# ESP32.net
KiCad netlist of a schematic drawn in Altium Designer
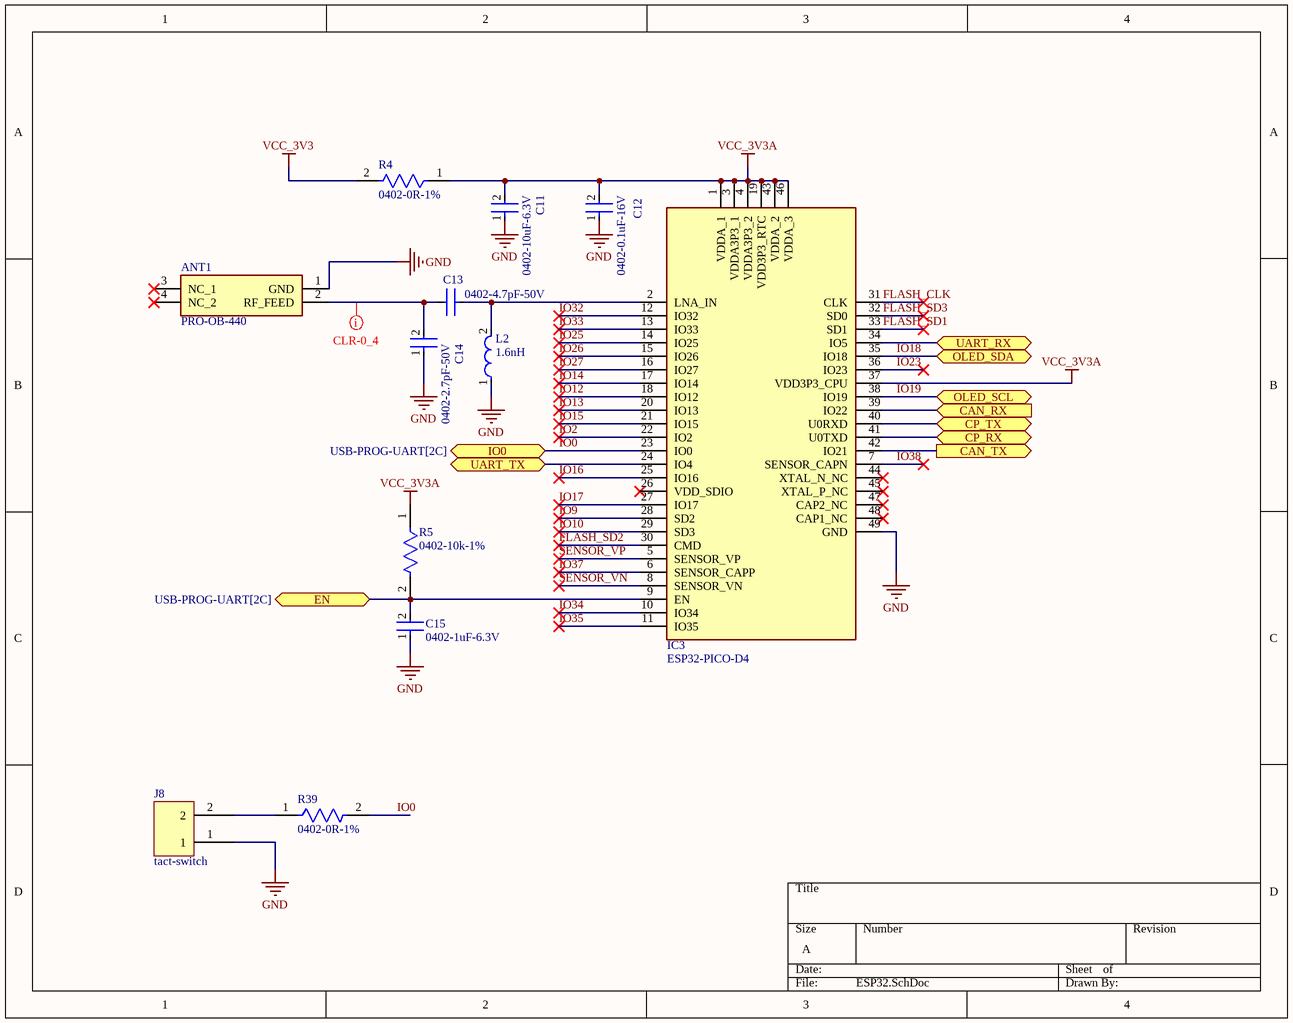
[diagram p0: ESP32.SchDoc]

(export (version "E")
  (design (tool "Eeschema 10.0.6"))
  (components
    (comp (ref "ANT1")
      (value "PRO-OB-440")
      (footprint "SamacSys:PRO-OB-440_1")
      (description "Antenna")
      (libsource (lib "SamacSys") (part "PRO-OB-440"))
    )
    (comp (ref "C11")
      (value "0402-10uF-6.3V")
      (footprint "FP-GRM155-0_05-IPC_A")
      (description "CAP CER 0.22UF 10V X5R 0402")
      (fields (field (name "VOLTAGE") "10V") (field (name "TOLERANCE") "10%"))
      (libsource (lib "Altium Content Vault") (part "02cd4be3c70576c341d710602a673aa"))
    )
    (comp (ref "C12")
      (value "0402-0.1uF-16V")
      (footprint "FP-GRM155-0_05-IPC_A")
      (description "CAP CER 0.22UF 10V X5R 0402")
      (fields (field (name "VOLTAGE") "10V") (field (name "TOLERANCE") "10%"))
      (libsource (lib "Altium Content Vault") (part "02cd4be3c70576c341d710602a673aa"))
    )
    (comp (ref "C13")
      (value "0402-4.7pF-50V")
      (footprint "FP-GRM155-0_05-IPC_A")
      (description "CAP CER 0.22UF 10V X5R 0402")
      (fields (field (name "VOLTAGE") "10V") (field (name "TOLERANCE") "10%"))
      (libsource (lib "") (part "02cd4be3c70576c341d710602a673aa_1"))
    )
    (comp (ref "C14")
      (value "0402-2.7pF-50V")
      (footprint "FP-GRM155-0_05-IPC_A")
      (description "CAP CER 0.22UF 10V X5R 0402")
      (fields (field (name "VOLTAGE") "10V") (field (name "TOLERANCE") "10%"))
      (libsource (lib "Altium Content Vault") (part "02cd4be3c70576c341d710602a673aa"))
    )
    (comp (ref "C15")
      (value "0402-1uF-6.3V")
      (footprint "FP-GRM155-0_05-IPC_A")
      (description "CAP CER 0.22UF 10V X5R 0402")
      (fields (field (name "VOLTAGE") "10V") (field (name "TOLERANCE") "10%"))
      (libsource (lib "Altium Content Vault") (part "02cd4be3c70576c341d710602a673aa"))
    )
    (comp (ref "IC3")
      (value "ESP32-PICO-D4")
      (footprint "ESP32PICOD4")
      (description "Integrated Circuit")
      (fields (field (name "MOUSER PART NUMBER") "356-ESP32-PICO-D4"))
      (libsource (lib "SamacSys") (part "ESP32-PICO-D4"))
    )
    (comp (ref "J8")
      (value "tact-switch")
      (footprint "tact-switch")
      (libsource (lib "Schlib1") (part "tact-switch"))
    )
    (comp (ref "L2")
      (value "1.6nH")
      (footprint "FP-LQW15AN_00-W0_6-0_1-MFG")
      (description "Wire Wound RF Inductor 3.9nH ±0.1nH 750mA 0.07Ω 0402 (1005)")
      (libsource (lib "Altium Content Vault") (part "725321dda6339637d4d059423bc1c3c"))
    )
    (comp (ref "R4")
      (value "0402-0R-1%")
      (footprint "FP-CRCW0402-e3-IPC_C")
      (description "RES Thick Film, 0Ω, 0.063W, 0402")
      (fields (field (name "TOLERANCE") "5%"))
      (libsource (lib "Altium Content Vault") (part "1029c3af85768c4190bb7ad29bc67b5"))
    )
    (comp (ref "R5")
      (value "0402-10k-1%")
      (footprint "FP-CRCW0402-e3-IPC_C")
      (description "RES Thick Film, 0Ω, 0.063W, 0402")
      (fields (field (name "TOLERANCE") "5%"))
      (libsource (lib "Altium Content Vault") (part "1029c3af85768c4190bb7ad29bc67b5"))
    )
    (comp (ref "R39")
      (value "0402-0R-1%")
      (footprint "FP-CRCW0402-e3-IPC_C")
      (description "RES Thick Film, 0Ω, 0.063W, 0402")
      (fields (field (name "TOLERANCE") "5%"))
      (libsource (lib "Altium Content Vault") (part "1029c3af85768c4190bb7ad29bc67b5"))
    )
  )
  (nets
    (net (code "1") (name "/CAN_RX") (class "Default")
      (node (ref "IC3") (pin "39") (pinfunction "IO22_39") (pintype "passive"))
    )
    (net (code "2") (name "/CAN_TX") (class "Default")
      (node (ref "IC3") (pin "42") (pinfunction "IO21_42") (pintype "passive"))
    )
    (net (code "3") (name "/CP_RX") (class "Default")
      (node (ref "IC3") (pin "41") (pinfunction "U0TXD_41") (pintype "passive"))
    )
    (net (code "4") (name "/CP_TX") (class "Default")
      (node (ref "IC3") (pin "40") (pinfunction "U0RXD_40") (pintype "passive"))
    )
    (net (code "5") (name "/EN") (class "Default")
      (node (ref "C15") (pin "2") (pinfunction "2_2") (pintype "passive"))
      (node (ref "IC3") (pin "9") (pinfunction "EN_9") (pintype "passive"))
      (node (ref "R5") (pin "2") (pinfunction "2_2") (pintype "passive"))
    )
    (net (code "6") (name "/FLASH_CLK") (class "Default")
      (node (ref "IC3") (pin "31") (pinfunction "CLK_31") (pintype "passive+no_connect"))
    )
    (net (code "7") (name "/FLASH_SD1") (class "Default")
      (node (ref "IC3") (pin "33") (pinfunction "SD1_33") (pintype "passive+no_connect"))
    )
    (net (code "8") (name "/FLASH_SD2") (class "Default")
      (node (ref "IC3") (pin "30") (pinfunction "CMD_30") (pintype "passive+no_connect"))
    )
    (net (code "9") (name "/FLASH_SD3") (class "Default")
      (node (ref "IC3") (pin "32") (pinfunction "SD0_32") (pintype "passive+no_connect"))
    )
    (net (code "10") (name "/IO0") (class "Default")
      (node (ref "IC3") (pin "23") (pinfunction "IO0_23") (pintype "passive"))
      (node (ref "R39") (pin "2") (pinfunction "2_2") (pintype "passive"))
    )
    (net (code "11") (name "/IO2") (class "Default")
      (node (ref "IC3") (pin "22") (pinfunction "IO2_22") (pintype "passive+no_connect"))
    )
    (net (code "12") (name "/IO9") (class "Default")
      (node (ref "IC3") (pin "28") (pinfunction "SD2_28") (pintype "passive+no_connect"))
    )
    (net (code "13") (name "/IO10") (class "Default")
      (node (ref "IC3") (pin "29") (pinfunction "SD3_29") (pintype "passive+no_connect"))
    )
    (net (code "14") (name "/IO12") (class "Default")
      (node (ref "IC3") (pin "18") (pinfunction "IO12_18") (pintype "passive+no_connect"))
    )
    (net (code "15") (name "/IO13") (class "Default")
      (node (ref "IC3") (pin "20") (pinfunction "IO13_20") (pintype "passive+no_connect"))
    )
    (net (code "16") (name "/IO14") (class "Default")
      (node (ref "IC3") (pin "17") (pinfunction "IO14_17") (pintype "passive+no_connect"))
    )
    (net (code "17") (name "/IO15") (class "Default")
      (node (ref "IC3") (pin "21") (pinfunction "IO15_21") (pintype "passive+no_connect"))
    )
    (net (code "18") (name "/IO16") (class "Default")
      (node (ref "IC3") (pin "25") (pinfunction "IO16_25") (pintype "passive+no_connect"))
    )
    (net (code "19") (name "/IO17") (class "Default")
      (node (ref "IC3") (pin "27") (pinfunction "IO17_27") (pintype "passive+no_connect"))
    )
    (net (code "20") (name "/IO18") (class "Default")
      (node (ref "IC3") (pin "35") (pinfunction "IO18_35") (pintype "passive"))
    )
    (net (code "21") (name "/IO19") (class "Default")
      (node (ref "IC3") (pin "38") (pinfunction "IO19_38") (pintype "passive"))
    )
    (net (code "22") (name "/IO23") (class "Default")
      (node (ref "IC3") (pin "36") (pinfunction "IO23_36") (pintype "passive+no_connect"))
    )
    (net (code "23") (name "/IO25") (class "Default")
      (node (ref "IC3") (pin "14") (pinfunction "IO25_14") (pintype "passive+no_connect"))
    )
    (net (code "24") (name "/IO26") (class "Default")
      (node (ref "IC3") (pin "15") (pinfunction "IO26_15") (pintype "passive+no_connect"))
    )
    (net (code "25") (name "/IO27") (class "Default")
      (node (ref "IC3") (pin "16") (pinfunction "IO27_16") (pintype "passive+no_connect"))
    )
    (net (code "26") (name "/IO32") (class "Default")
      (node (ref "IC3") (pin "12") (pinfunction "IO32_12") (pintype "passive+no_connect"))
    )
    (net (code "27") (name "/IO33") (class "Default")
      (node (ref "IC3") (pin "13") (pinfunction "IO33_13") (pintype "passive+no_connect"))
    )
    (net (code "28") (name "/IO34") (class "Default")
      (node (ref "IC3") (pin "10") (pinfunction "IO34_10") (pintype "passive+no_connect"))
    )
    (net (code "29") (name "/IO35") (class "Default")
      (node (ref "IC3") (pin "11") (pinfunction "IO35_11") (pintype "passive+no_connect"))
    )
    (net (code "30") (name "/IO37") (class "Default")
      (node (ref "IC3") (pin "6") (pinfunction "SENSOR_CAPP_6") (pintype "passive+no_connect"))
    )
    (net (code "31") (name "/IO38") (class "Default")
      (node (ref "IC3") (pin "7") (pinfunction "SENSOR_CAPN_7") (pintype "passive+no_connect"))
    )
    (net (code "32") (name "/SENSOR_VN") (class "Default")
      (node (ref "IC3") (pin "8") (pinfunction "SENSOR_VN_8") (pintype "passive+no_connect"))
    )
    (net (code "33") (name "/SENSOR_VP") (class "Default")
      (node (ref "IC3") (pin "5") (pinfunction "SENSOR_VP_5") (pintype "passive+no_connect"))
    )
    (net (code "34") (name "/UART_RX") (class "Default")
      (node (ref "IC3") (pin "34") (pinfunction "IO5_34") (pintype "passive"))
    )
    (net (code "35") (name "/UART_TX") (class "Default")
      (node (ref "IC3") (pin "24") (pinfunction "IO4_24") (pintype "passive"))
    )
    (net (code "36") (name "GND") (class "Default")
      (node (ref "ANT1") (pin "1") (pinfunction "GND_1") (pintype "passive"))
      (node (ref "C11") (pin "1") (pinfunction "1_1") (pintype "passive"))
      (node (ref "C12") (pin "1") (pinfunction "1_1") (pintype "passive"))
      (node (ref "C14") (pin "1") (pinfunction "1_1") (pintype "passive"))
      (node (ref "C15") (pin "1") (pinfunction "1_1") (pintype "passive"))
      (node (ref "IC3") (pin "49") (pinfunction "GND_49") (pintype "passive"))
      (node (ref "J8") (pin "1") (pinfunction "1_1") (pintype "passive"))
      (node (ref "L2") (pin "1") (pinfunction "1_1") (pintype "passive"))
    )
    (net (code "37") (name "Net-(ANT1-RF_FEED)") (class "Default")
      (node (ref "ANT1") (pin "2") (pinfunction "RF_FEED_2") (pintype "passive"))
      (node (ref "C13") (pin "2") (pinfunction "2_2") (pintype "passive"))
      (node (ref "C14") (pin "2") (pinfunction "2_2") (pintype "passive"))
    )
    (net (code "38") (name "Net-(IC3-LNA_IN)") (class "Default")
      (node (ref "C13") (pin "1") (pinfunction "1_1") (pintype "passive"))
      (node (ref "IC3") (pin "2") (pinfunction "LNA_IN_2") (pintype "passive"))
      (node (ref "L2") (pin "2") (pinfunction "2_2") (pintype "passive"))
    )
    (net (code "39") (name "Net-(J8-Pad2)") (class "Default")
      (node (ref "J8") (pin "2") (pinfunction "2_2") (pintype "passive"))
      (node (ref "R39") (pin "1") (pinfunction "1_1") (pintype "passive"))
    )
    (net (code "40") (name "VCC_3V3") (class "Default")
      (node (ref "R4") (pin "2") (pinfunction "2_2") (pintype "passive"))
    )
    (net (code "41") (name "VCC_3V3A") (class "Default")
      (node (ref "C11") (pin "2") (pinfunction "2_2") (pintype "passive"))
      (node (ref "C12") (pin "2") (pinfunction "2_2") (pintype "passive"))
      (node (ref "IC3") (pin "1") (pinfunction "VDDA_1_1") (pintype "passive"))
      (node (ref "IC3") (pin "19") (pinfunction "VDD3P3_RTC_19") (pintype "passive"))
      (node (ref "IC3") (pin "3") (pinfunction "VDDA3P3_1_3") (pintype "passive"))
      (node (ref "IC3") (pin "37") (pinfunction "VDD3P3_CPU_37") (pintype "passive"))
      (node (ref "IC3") (pin "4") (pinfunction "VDDA3P3_2_4") (pintype "passive"))
      (node (ref "IC3") (pin "43") (pinfunction "VDDA_2_43") (pintype "passive"))
      (node (ref "IC3") (pin "46") (pinfunction "VDDA_3_46") (pintype "passive"))
      (node (ref "R4") (pin "1") (pinfunction "1_1") (pintype "passive"))
      (node (ref "R5") (pin "1") (pinfunction "1_1") (pintype "passive"))
    )
    (net (code "42") (name "unconnected-(ANT1-NC_1-Pad3)") (class "Default")
      (node (ref "ANT1") (pin "3") (pinfunction "NC_1_3") (pintype "passive+no_connect"))
    )
    (net (code "43") (name "unconnected-(ANT1-NC_2-Pad4)") (class "Default")
      (node (ref "ANT1") (pin "4") (pinfunction "NC_2_4") (pintype "passive+no_connect"))
    )
    (net (code "44") (name "unconnected-(IC3-CAP1_NC-Pad48)") (class "Default")
      (node (ref "IC3") (pin "48") (pinfunction "CAP1_NC_48") (pintype "passive+no_connect"))
    )
    (net (code "45") (name "unconnected-(IC3-CAP2_NC-Pad47)") (class "Default")
      (node (ref "IC3") (pin "47") (pinfunction "CAP2_NC_47") (pintype "passive+no_connect"))
    )
    (net (code "46") (name "unconnected-(IC3-VDD_SDIO-Pad26)") (class "Default")
      (node (ref "IC3") (pin "26") (pinfunction "VDD_SDIO_26") (pintype "passive+no_connect"))
    )
    (net (code "47") (name "unconnected-(IC3-XTAL_N_NC-Pad44)") (class "Default")
      (node (ref "IC3") (pin "44") (pinfunction "XTAL_N_NC_44") (pintype "passive+no_connect"))
    )
    (net (code "48") (name "unconnected-(IC3-XTAL_P_NC-Pad45)") (class "Default")
      (node (ref "IC3") (pin "45") (pinfunction "XTAL_P_NC_45") (pintype "passive+no_connect"))
    )
  )
)
